# RGB.net
KiCad netlist of a schematic drawn in EasyEDA
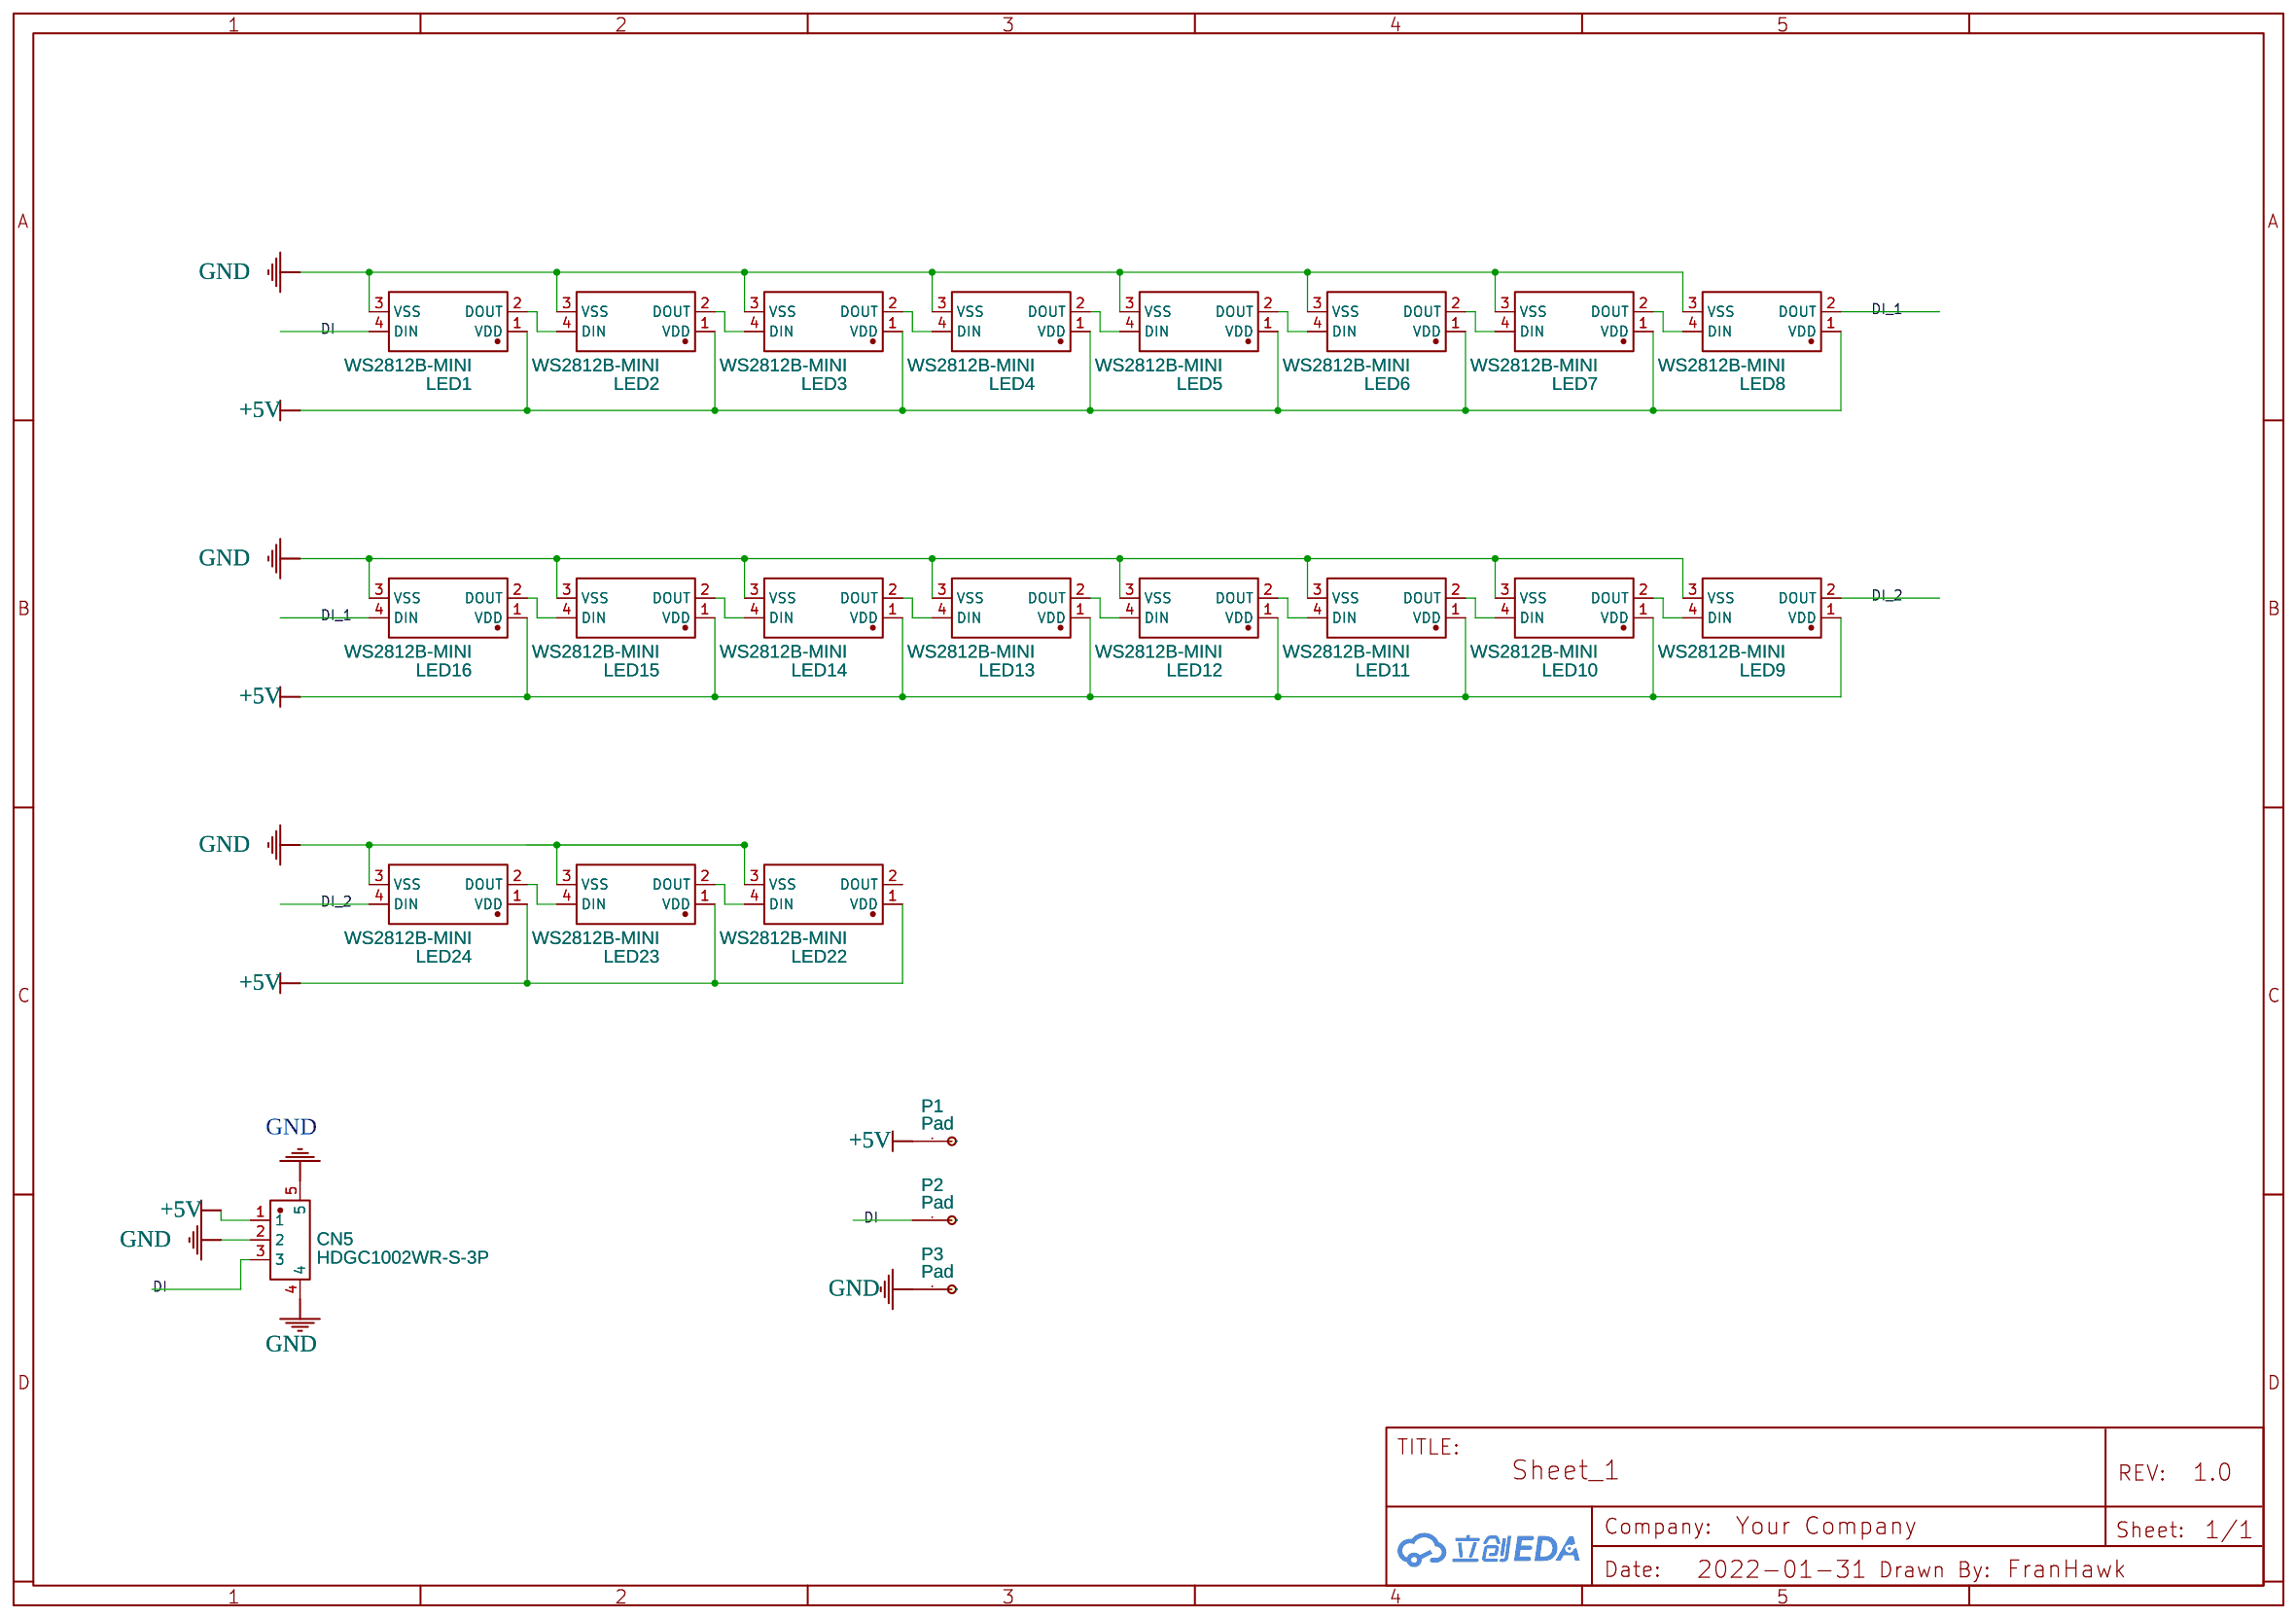
[diagram p0: schematic sheet]

(export (version "E")
  (design (tool "Eeschema 10.0.6"))
  (components
    (comp (ref "CN5")
      (value "HDGC1002WR-S-3P")
      (fields (field (name "BOM_Supplier Part") "C2936213"))
      (libsource (lib "") (part "HDGC1002WR-S-3P"))
    )
    (comp (ref "LED1")
      (value "WS2812B-MINI")
      (fields
        (field (name "BOM_Manufacturer Part") "WS2812B-Mini")
        (field (name "BOM_Supplier Part") "C527089")
      )
      (libsource (lib "") (part "WS2812B-MINI"))
    )
    (comp (ref "LED2")
      (value "WS2812B-MINI")
      (fields
        (field (name "BOM_Manufacturer Part") "WS2812B-Mini")
        (field (name "BOM_Supplier Part") "C527089")
      )
      (libsource (lib "") (part "WS2812B-MINI"))
    )
    (comp (ref "LED3")
      (value "WS2812B-MINI")
      (fields
        (field (name "BOM_Manufacturer Part") "WS2812B-Mini")
        (field (name "BOM_Supplier Part") "C527089")
      )
      (libsource (lib "") (part "WS2812B-MINI"))
    )
    (comp (ref "LED4")
      (value "WS2812B-MINI")
      (fields
        (field (name "BOM_Manufacturer Part") "WS2812B-Mini")
        (field (name "BOM_Supplier Part") "C527089")
      )
      (libsource (lib "") (part "WS2812B-MINI"))
    )
    (comp (ref "LED5")
      (value "WS2812B-MINI")
      (fields
        (field (name "BOM_Manufacturer Part") "WS2812B-Mini")
        (field (name "BOM_Supplier Part") "C527089")
      )
      (libsource (lib "") (part "WS2812B-MINI"))
    )
    (comp (ref "LED6")
      (value "WS2812B-MINI")
      (fields
        (field (name "BOM_Manufacturer Part") "WS2812B-Mini")
        (field (name "BOM_Supplier Part") "C527089")
      )
      (libsource (lib "") (part "WS2812B-MINI"))
    )
    (comp (ref "LED7")
      (value "WS2812B-MINI")
      (fields
        (field (name "BOM_Manufacturer Part") "WS2812B-Mini")
        (field (name "BOM_Supplier Part") "C527089")
      )
      (libsource (lib "") (part "WS2812B-MINI"))
    )
    (comp (ref "LED8")
      (value "WS2812B-MINI")
      (fields
        (field (name "BOM_Manufacturer Part") "WS2812B-Mini")
        (field (name "BOM_Supplier Part") "C527089")
      )
      (libsource (lib "") (part "WS2812B-MINI"))
    )
    (comp (ref "LED9")
      (value "WS2812B-MINI")
      (fields
        (field (name "BOM_Manufacturer Part") "WS2812B-Mini")
        (field (name "BOM_Supplier Part") "C527089")
      )
      (libsource (lib "") (part "WS2812B-MINI"))
    )
    (comp (ref "LED10")
      (value "WS2812B-MINI")
      (fields
        (field (name "BOM_Manufacturer Part") "WS2812B-Mini")
        (field (name "BOM_Supplier Part") "C527089")
      )
      (libsource (lib "") (part "WS2812B-MINI"))
    )
    (comp (ref "LED11")
      (value "WS2812B-MINI")
      (fields
        (field (name "BOM_Manufacturer Part") "WS2812B-Mini")
        (field (name "BOM_Supplier Part") "C527089")
      )
      (libsource (lib "") (part "WS2812B-MINI"))
    )
    (comp (ref "LED12")
      (value "WS2812B-MINI")
      (fields
        (field (name "BOM_Manufacturer Part") "WS2812B-Mini")
        (field (name "BOM_Supplier Part") "C527089")
      )
      (libsource (lib "") (part "WS2812B-MINI"))
    )
    (comp (ref "LED13")
      (value "WS2812B-MINI")
      (fields
        (field (name "BOM_Manufacturer Part") "WS2812B-Mini")
        (field (name "BOM_Supplier Part") "C527089")
      )
      (libsource (lib "") (part "WS2812B-MINI"))
    )
    (comp (ref "LED14")
      (value "WS2812B-MINI")
      (fields
        (field (name "BOM_Manufacturer Part") "WS2812B-Mini")
        (field (name "BOM_Supplier Part") "C527089")
      )
      (libsource (lib "") (part "WS2812B-MINI"))
    )
    (comp (ref "LED15")
      (value "WS2812B-MINI")
      (fields
        (field (name "BOM_Manufacturer Part") "WS2812B-Mini")
        (field (name "BOM_Supplier Part") "C527089")
      )
      (libsource (lib "") (part "WS2812B-MINI"))
    )
    (comp (ref "LED16")
      (value "WS2812B-MINI")
      (fields
        (field (name "BOM_Manufacturer Part") "WS2812B-Mini")
        (field (name "BOM_Supplier Part") "C527089")
      )
      (libsource (lib "") (part "WS2812B-MINI"))
    )
    (comp (ref "LED22")
      (value "WS2812B-MINI")
      (fields
        (field (name "BOM_Manufacturer Part") "WS2812B-Mini")
        (field (name "BOM_Supplier Part") "C527089")
      )
      (libsource (lib "") (part "WS2812B-MINI"))
    )
    (comp (ref "LED23")
      (value "WS2812B-MINI")
      (fields
        (field (name "BOM_Manufacturer Part") "WS2812B-Mini")
        (field (name "BOM_Supplier Part") "C527089")
      )
      (libsource (lib "") (part "WS2812B-MINI"))
    )
    (comp (ref "LED24")
      (value "WS2812B-MINI")
      (fields
        (field (name "BOM_Manufacturer Part") "WS2812B-Mini")
        (field (name "BOM_Supplier Part") "C527089")
      )
      (libsource (lib "") (part "WS2812B-MINI"))
    )
    (comp (ref "P1") (value "Pad") (libsource (lib "") (part "Pad")))
    (comp (ref "P2") (value "Pad") (libsource (lib "") (part "Pad")))
    (comp (ref "P3") (value "Pad") (libsource (lib "") (part "Pad")))
  )
  (nets
    (net (code "1") (name "+5V") (class "Default")
      (node (ref "CN5") (pin "1") (pinfunction "1_1") (pintype "unspecified"))
      (node (ref "LED1") (pin "1") (pinfunction "VDD_1") (pintype "unspecified"))
      (node (ref "LED10") (pin "1") (pinfunction "VDD_1") (pintype "unspecified"))
      (node (ref "LED11") (pin "1") (pinfunction "VDD_1") (pintype "unspecified"))
      (node (ref "LED12") (pin "1") (pinfunction "VDD_1") (pintype "unspecified"))
      (node (ref "LED13") (pin "1") (pinfunction "VDD_1") (pintype "unspecified"))
      (node (ref "LED14") (pin "1") (pinfunction "VDD_1") (pintype "unspecified"))
      (node (ref "LED15") (pin "1") (pinfunction "VDD_1") (pintype "unspecified"))
      (node (ref "LED16") (pin "1") (pinfunction "VDD_1") (pintype "unspecified"))
      (node (ref "LED2") (pin "1") (pinfunction "VDD_1") (pintype "unspecified"))
      (node (ref "LED22") (pin "1") (pinfunction "VDD_1") (pintype "unspecified"))
      (node (ref "LED23") (pin "1") (pinfunction "VDD_1") (pintype "unspecified"))
      (node (ref "LED24") (pin "1") (pinfunction "VDD_1") (pintype "unspecified"))
      (node (ref "LED3") (pin "1") (pinfunction "VDD_1") (pintype "unspecified"))
      (node (ref "LED4") (pin "1") (pinfunction "VDD_1") (pintype "unspecified"))
      (node (ref "LED5") (pin "1") (pinfunction "VDD_1") (pintype "unspecified"))
      (node (ref "LED6") (pin "1") (pinfunction "VDD_1") (pintype "unspecified"))
      (node (ref "LED7") (pin "1") (pinfunction "VDD_1") (pintype "unspecified"))
      (node (ref "LED8") (pin "1") (pinfunction "VDD_1") (pintype "unspecified"))
      (node (ref "LED9") (pin "1") (pinfunction "VDD_1") (pintype "unspecified"))
      (node (ref "P1") (pin "1") (pinfunction "1_1") (pintype "unspecified"))
    )
    (net (code "2") (name "/DI") (class "Default")
      (node (ref "CN5") (pin "3") (pinfunction "3_3") (pintype "unspecified"))
      (node (ref "LED1") (pin "4") (pinfunction "DIN_4") (pintype "unspecified"))
      (node (ref "P2") (pin "1") (pinfunction "1_1") (pintype "unspecified"))
    )
    (net (code "3") (name "/DI_1") (class "Default")
      (node (ref "LED16") (pin "4") (pinfunction "DIN_4") (pintype "unspecified"))
      (node (ref "LED8") (pin "2") (pinfunction "DOUT_2") (pintype "unspecified"))
    )
    (net (code "4") (name "/DI_2") (class "Default")
      (node (ref "LED24") (pin "4") (pinfunction "DIN_4") (pintype "unspecified"))
      (node (ref "LED9") (pin "2") (pinfunction "DOUT_2") (pintype "unspecified"))
    )
    (net (code "5") (name "GND") (class "Default")
      (node (ref "CN5") (pin "2") (pinfunction "2_2") (pintype "unspecified"))
      (node (ref "CN5") (pin "4") (pinfunction "4_4") (pintype "unspecified"))
      (node (ref "CN5") (pin "5") (pinfunction "5_5") (pintype "unspecified"))
      (node (ref "LED1") (pin "3") (pinfunction "VSS_3") (pintype "unspecified"))
      (node (ref "LED10") (pin "3") (pinfunction "VSS_3") (pintype "unspecified"))
      (node (ref "LED11") (pin "3") (pinfunction "VSS_3") (pintype "unspecified"))
      (node (ref "LED12") (pin "3") (pinfunction "VSS_3") (pintype "unspecified"))
      (node (ref "LED13") (pin "3") (pinfunction "VSS_3") (pintype "unspecified"))
      (node (ref "LED14") (pin "3") (pinfunction "VSS_3") (pintype "unspecified"))
      (node (ref "LED15") (pin "3") (pinfunction "VSS_3") (pintype "unspecified"))
      (node (ref "LED16") (pin "3") (pinfunction "VSS_3") (pintype "unspecified"))
      (node (ref "LED2") (pin "3") (pinfunction "VSS_3") (pintype "unspecified"))
      (node (ref "LED22") (pin "3") (pinfunction "VSS_3") (pintype "unspecified"))
      (node (ref "LED23") (pin "3") (pinfunction "VSS_3") (pintype "unspecified"))
      (node (ref "LED24") (pin "3") (pinfunction "VSS_3") (pintype "unspecified"))
      (node (ref "LED3") (pin "3") (pinfunction "VSS_3") (pintype "unspecified"))
      (node (ref "LED4") (pin "3") (pinfunction "VSS_3") (pintype "unspecified"))
      (node (ref "LED5") (pin "3") (pinfunction "VSS_3") (pintype "unspecified"))
      (node (ref "LED6") (pin "3") (pinfunction "VSS_3") (pintype "unspecified"))
      (node (ref "LED7") (pin "3") (pinfunction "VSS_3") (pintype "unspecified"))
      (node (ref "LED8") (pin "3") (pinfunction "VSS_3") (pintype "unspecified"))
      (node (ref "LED9") (pin "3") (pinfunction "VSS_3") (pintype "unspecified"))
      (node (ref "P3") (pin "1") (pinfunction "1_1") (pintype "unspecified"))
    )
    (net (code "6") (name "Net-(LED1-DOUT)") (class "Default")
      (node (ref "LED1") (pin "2") (pinfunction "DOUT_2") (pintype "unspecified"))
      (node (ref "LED2") (pin "4") (pinfunction "DIN_4") (pintype "unspecified"))
    )
    (net (code "7") (name "Net-(LED2-DOUT)") (class "Default")
      (node (ref "LED2") (pin "2") (pinfunction "DOUT_2") (pintype "unspecified"))
      (node (ref "LED3") (pin "4") (pinfunction "DIN_4") (pintype "unspecified"))
    )
    (net (code "8") (name "Net-(LED3-DOUT)") (class "Default")
      (node (ref "LED3") (pin "2") (pinfunction "DOUT_2") (pintype "unspecified"))
      (node (ref "LED4") (pin "4") (pinfunction "DIN_4") (pintype "unspecified"))
    )
    (net (code "9") (name "Net-(LED4-DOUT)") (class "Default")
      (node (ref "LED4") (pin "2") (pinfunction "DOUT_2") (pintype "unspecified"))
      (node (ref "LED5") (pin "4") (pinfunction "DIN_4") (pintype "unspecified"))
    )
    (net (code "10") (name "Net-(LED5-DOUT)") (class "Default")
      (node (ref "LED5") (pin "2") (pinfunction "DOUT_2") (pintype "unspecified"))
      (node (ref "LED6") (pin "4") (pinfunction "DIN_4") (pintype "unspecified"))
    )
    (net (code "11") (name "Net-(LED6-DOUT)") (class "Default")
      (node (ref "LED6") (pin "2") (pinfunction "DOUT_2") (pintype "unspecified"))
      (node (ref "LED7") (pin "4") (pinfunction "DIN_4") (pintype "unspecified"))
    )
    (net (code "12") (name "Net-(LED7-DOUT)") (class "Default")
      (node (ref "LED7") (pin "2") (pinfunction "DOUT_2") (pintype "unspecified"))
      (node (ref "LED8") (pin "4") (pinfunction "DIN_4") (pintype "unspecified"))
    )
    (net (code "13") (name "Net-(LED10-DIN)") (class "Default")
      (node (ref "LED10") (pin "4") (pinfunction "DIN_4") (pintype "unspecified"))
      (node (ref "LED11") (pin "2") (pinfunction "DOUT_2") (pintype "unspecified"))
    )
    (net (code "14") (name "Net-(LED10-DOUT)") (class "Default")
      (node (ref "LED10") (pin "2") (pinfunction "DOUT_2") (pintype "unspecified"))
      (node (ref "LED9") (pin "4") (pinfunction "DIN_4") (pintype "unspecified"))
    )
    (net (code "15") (name "Net-(LED11-DIN)") (class "Default")
      (node (ref "LED11") (pin "4") (pinfunction "DIN_4") (pintype "unspecified"))
      (node (ref "LED12") (pin "2") (pinfunction "DOUT_2") (pintype "unspecified"))
    )
    (net (code "16") (name "Net-(LED12-DIN)") (class "Default")
      (node (ref "LED12") (pin "4") (pinfunction "DIN_4") (pintype "unspecified"))
      (node (ref "LED13") (pin "2") (pinfunction "DOUT_2") (pintype "unspecified"))
    )
    (net (code "17") (name "Net-(LED13-DIN)") (class "Default")
      (node (ref "LED13") (pin "4") (pinfunction "DIN_4") (pintype "unspecified"))
      (node (ref "LED14") (pin "2") (pinfunction "DOUT_2") (pintype "unspecified"))
    )
    (net (code "18") (name "Net-(LED14-DIN)") (class "Default")
      (node (ref "LED14") (pin "4") (pinfunction "DIN_4") (pintype "unspecified"))
      (node (ref "LED15") (pin "2") (pinfunction "DOUT_2") (pintype "unspecified"))
    )
    (net (code "19") (name "Net-(LED15-DIN)") (class "Default")
      (node (ref "LED15") (pin "4") (pinfunction "DIN_4") (pintype "unspecified"))
      (node (ref "LED16") (pin "2") (pinfunction "DOUT_2") (pintype "unspecified"))
    )
    (net (code "20") (name "Net-(LED22-DIN)") (class "Default")
      (node (ref "LED22") (pin "4") (pinfunction "DIN_4") (pintype "unspecified"))
      (node (ref "LED23") (pin "2") (pinfunction "DOUT_2") (pintype "unspecified"))
    )
    (net (code "21") (name "Net-(LED23-DIN)") (class "Default")
      (node (ref "LED23") (pin "4") (pinfunction "DIN_4") (pintype "unspecified"))
      (node (ref "LED24") (pin "2") (pinfunction "DOUT_2") (pintype "unspecified"))
    )
    (net (code "22") (name "unconnected-(LED22-DOUT-Pad2)") (class "Default")
      (node (ref "LED22") (pin "2") (pinfunction "DOUT_2") (pintype "unspecified"))
    )
  )
)
